# MAIN.net
KiCad netlist of a schematic drawn in Altium Designer
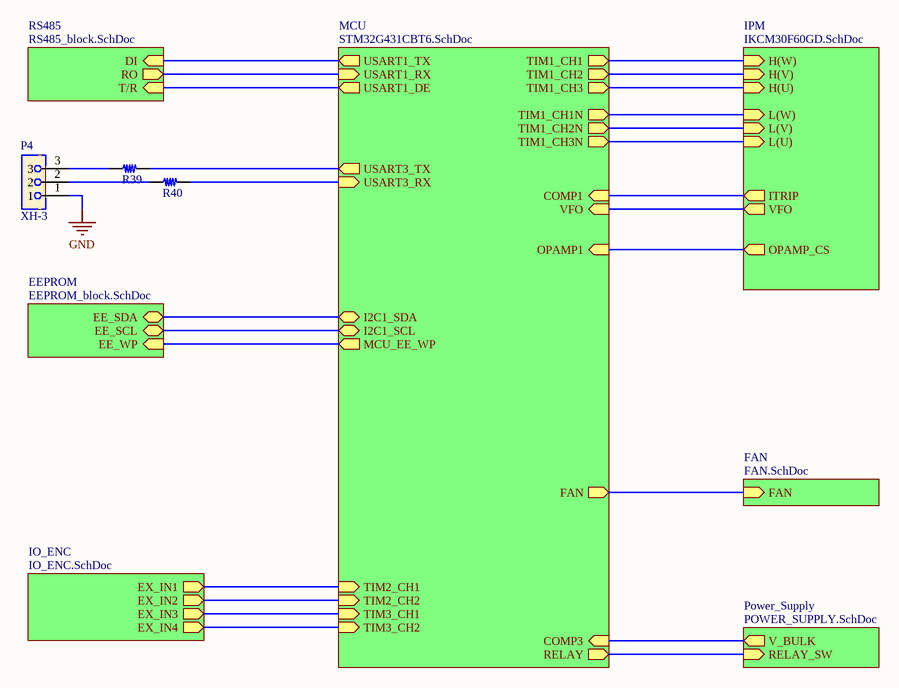
[diagram p0: MAIN.SchDoc]

(export (version "E")
  (design (tool "Eeschema 10.0.6"))
  (components
    (comp (ref "P4") (value "XH-3") (footprint "XH-3") (libsource (lib "radmehr_library") (part "XH-3")))
    (comp (ref "R39")
      (value "RES_SMD")
      (footprint "R 0603")
      (libsource (lib "radmehr_library") (part "RES_SMD"))
    )
    (comp (ref "R40")
      (value "RES_SMD")
      (footprint "R 0603")
      (libsource (lib "radmehr_library") (part "RES_SMD"))
    )
  )
  (nets
    (net (code "21") (name "/USART3_RX") (class "Default")
      (node (ref "R40") (pin "2") (pinfunction "2_2") (pintype "passive"))
    )
    (net (code "22") (name "/USART3_TX") (class "Default")
      (node (ref "R39") (pin "2") (pinfunction "2_2") (pintype "passive"))
    )
    (net (code "25") (name "GND") (class "Default")
      (node (ref "P4") (pin "1") (pinfunction "1_1") (pintype "passive"))
    )
    (net (code "26") (name "Net-(P4-Pad2)") (class "Default")
      (node (ref "P4") (pin "2") (pinfunction "2_2") (pintype "passive"))
      (node (ref "R40") (pin "1") (pinfunction "1_1") (pintype "passive"))
    )
    (net (code "27") (name "Net-(P4-Pad3)") (class "Default")
      (node (ref "P4") (pin "3") (pinfunction "3_3") (pintype "passive"))
      (node (ref "R39") (pin "1") (pinfunction "1_1") (pintype "passive"))
    )
  )
)
